# DCDC-LMR16030.net
KiCad netlist of a schematic drawn in Altium Designer
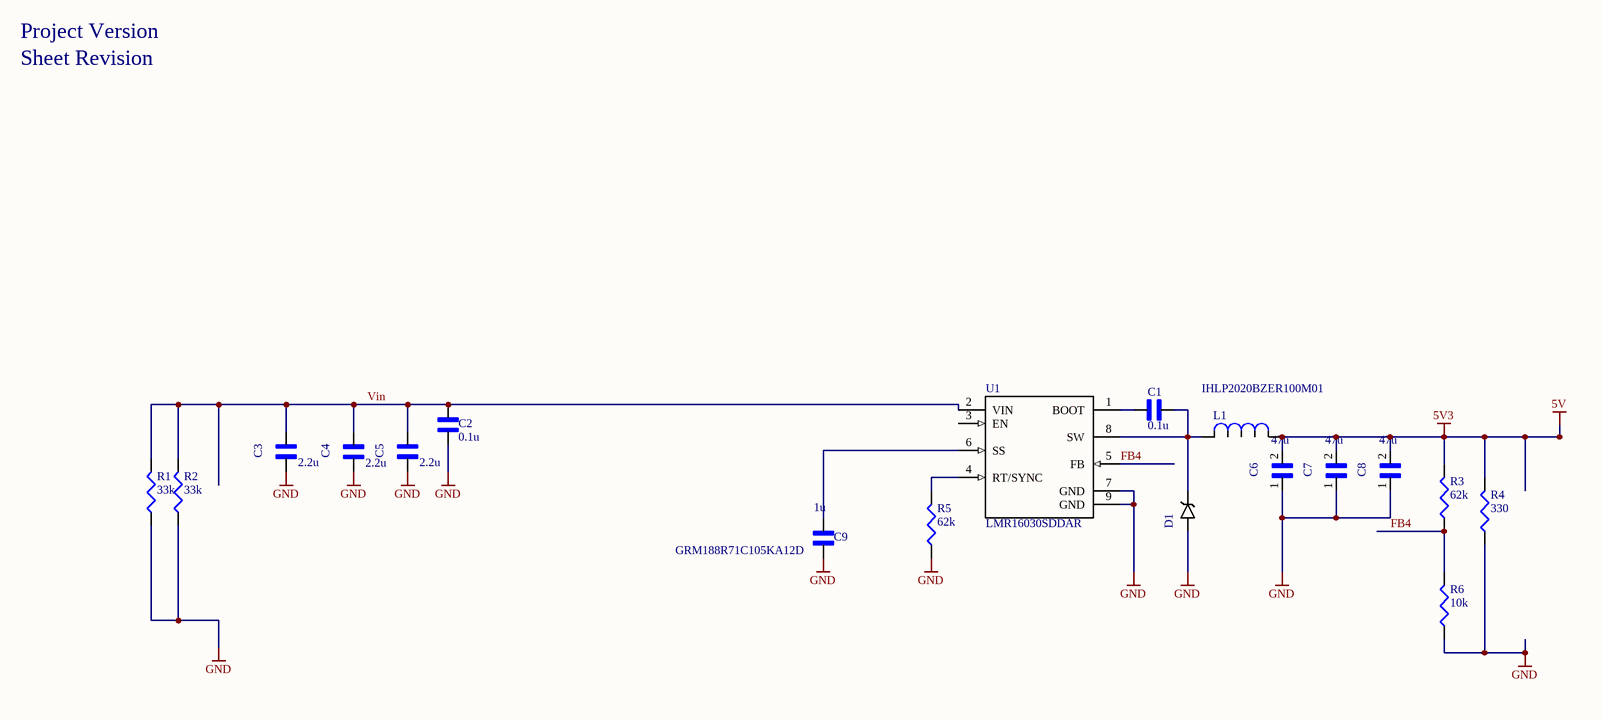
[diagram p0: DCDC-LMR16030.SchDoc]

(export (version "E")
  (design (tool "Eeschema 10.0.6"))
  (components
    (comp (ref "C1")
      (value "0.1u")
      (footprint "CAPC1005X55N")
      (description "GCM155R71H104KE02D, Чип 0402 X7R 0.1uF +10% 50V,Конденсатор")
      (fields (field (name "MF") "Murata") (field (name "MP") "GCM155R71H104KE02D"))
      (libsource (lib "") (part "GCM155R71H104KE02D_1"))
    )
    (comp (ref "C2")
      (value "0.1u")
      (footprint "CAPC1005X55N")
      (description "GCM155R71H104KE02D, Чип 0402 X7R 0.1uF +10% 50V,Конденсатор")
      (fields (field (name "MF") "Murata") (field (name "MP") "GCM155R71H104KE02D"))
      (libsource (lib "lib") (part "GCM155R71H104KE02D"))
    )
    (comp (ref "C3")
      (value "2.2u")
      (footprint "*CAP3216X125N")
      (description "1206 2.2 uF 50 V В±10% Tolerance X7R SMT Multilayer Ceramic Capacitor")
      (fields (field (name "MF") "Murata Electronics") (field (name "MP") "GRM31CR71H225KA88L"))
      (libsource (lib "lib") (part "GRM31CR71H225KA88L"))
    )
    (comp (ref "C4")
      (value "2.2u")
      (footprint "*CAP3216X125N")
      (description "1206 2.2 uF 50 V В±10% Tolerance X7R SMT Multilayer Ceramic Capacitor")
      (fields (field (name "MF") "Murata Electronics") (field (name "MP") "GRM31CR71H225KA88L"))
      (libsource (lib "lib") (part "GRM31CR71H225KA88L"))
    )
    (comp (ref "C5")
      (value "2.2u")
      (footprint "*CAP3216X125N")
      (description "1206 2.2 uF 50 V В±10% Tolerance X7R SMT Multilayer Ceramic Capacitor")
      (fields (field (name "MF") "Murata Electronics") (field (name "MP") "GRM31CR71H225KA88L"))
      (libsource (lib "lib") (part "GRM31CR71H225KA88L"))
    )
    (comp (ref "C6")
      (value "47u")
      (footprint "*CAPC3216X125N")
      (description "Multilayer Ceramic Capacitor, GRM Series, 47 - F, - 10%, X5R, 10 V, 1206 [3216 Metric]")
      (fields (field (name "MF") "Murata Electronics") (field (name "MP") "GRM31CR61A476KE15L"))
      (libsource (lib "lib") (part "GRM31CR61A476KE15L"))
    )
    (comp (ref "C7")
      (value "47u")
      (footprint "*CAPC3216X125N")
      (description "Multilayer Ceramic Capacitor, GRM Series, 47 - F, - 10%, X5R, 10 V, 1206 [3216 Metric]")
      (fields (field (name "MF") "Murata Electronics") (field (name "MP") "GRM31CR61A476KE15L"))
      (libsource (lib "lib") (part "GRM31CR61A476KE15L"))
    )
    (comp (ref "C8")
      (value "47u")
      (footprint "*CAPC3216X125N")
      (description "Multilayer Ceramic Capacitor, GRM Series, 47 - F, - 10%, X5R, 10 V, 1206 [3216 Metric]")
      (fields (field (name "MF") "Murata Electronics") (field (name "MP") "GRM31CR61A476KE15L"))
      (libsource (lib "lib") (part "GRM31CR61A476KE15L"))
    )
    (comp (ref "C9")
      (value "GRM188R71C105KA12D")
      (footprint "CAPC1608X90N")
      (description "SMD Capacitor X7R(EIA) with Capacitance: 1.0uF Tol. 10%. Rated Voltage: 16Vdc")
      (fields (field (name "MF") "Murata Electronics") (field (name "ALTIUM_VALUE") "1u"))
      (libsource (lib "lib") (part "GRM188R71C105KA12D"))
    )
    (comp (ref "D1")
      (value "SK56")
      (footprint "*SMB_P6SMB62AT3G(Primary)")
      (description "Диод Шоттки 5А 60В [SMB / DO-214AA]")
      (fields (field (name "MP") "SK56B") (field (name "MF") "Littelfuse Inc."))
      (libsource (lib "lib") (part "SK56"))
    )
    (comp (ref "L1")
      (value "IHLP2020BZER100M01")
      (footprint "IHLP")
      (description "10ÂµH Shielded Molded Inductor 2.3A 199mOhm Max Nonstandard")
      (fields (field (name "MF") "Vishay Dale"))
      (libsource (lib "lib") (part "IHLP2020BZER100M01"))
    )
    (comp (ref "R1")
      (value "33k")
      (footprint "J1-0603")
      (description "33 kOhms ±1% 0.1W, 1/10W Chip Resistor 0603 (1608 Metric) Moisture Resistant Thick Film")
      (fields (field (name "MF") "Yageo or NXP") (field (name "MP") "RC0603FR-0733KL"))
      (libsource (lib "lib") (part "RC0603FR-0733KL"))
    )
    (comp (ref "R2")
      (value "33k")
      (footprint "J1-0603")
      (description "33 kOhms ±1% 0.1W, 1/10W Chip Resistor 0603 (1608 Metric) Moisture Resistant Thick Film")
      (fields (field (name "MF") "Yageo or NXP") (field (name "MP") "RC0603FR-0733KL"))
      (libsource (lib "lib") (part "RC0603FR-0733KL"))
    )
    (comp (ref "R3")
      (value "62k")
      (footprint "RESC1005X40N")
      (description "0.062Вт 0402 62 кОм, 1%, Чип резистор (SMD)")
      (fields (field (name "MF") "Yageo or NXP") (field (name "MP") "RC0402FR-0762KL"))
      (libsource (lib "lib") (part "RC0402FR-0762KL"))
    )
    (comp (ref "R4")
      (value "330")
      (footprint "J1-0603")
      (description "330 Ohms ±1% 0.1W, 1/10W Chip Resistor 0603 (1608 Metric) Thick Film")
      (fields (field (name "MF") "Yageo or NXP") (field (name "MP") "RC0603FR-07330RL"))
      (libsource (lib "lib") (part "RC0603FR-07330RL"))
    )
    (comp (ref "R5")
      (value "62k")
      (footprint "RESC1005X40N")
      (description "0.062Вт 0402 62 кОм, 1%, Чип резистор (SMD)")
      (fields (field (name "MF") "Yageo or NXP") (field (name "MP") "RC0402FR-0762KL"))
      (libsource (lib "lib") (part "RC0402FR-0762KL"))
    )
    (comp (ref "R6")
      (value "10k")
      (footprint "RESC1005X40N")
      (description "0.062Вт 0402 10 кОм, 1%, Чип резистор (SMD)")
      (fields (field (name "MF") "Yageo or NXP") (field (name "MP") "RC0402FR-0710KL"))
      (libsource (lib "lib") (part "RC0402FR-0710KL"))
    )
    (comp (ref "U1")
      (value "LMR16030SDDAR")
      (footprint "*SOIC127P600X170-9N - duplicate")
      (fields (field (name "MF") "Texas Instruments"))
      (libsource (lib "lib") (part "LMR16030SDDAR"))
    )
  )
  (nets
    (net (code "1") (name "/FB4") (class "Default")
      (node (ref "R3") (pin "1") (pinfunction "1_1") (pintype "passive"))
      (node (ref "R6") (pin "2") (pinfunction "2_2") (pintype "passive"))
      (node (ref "U1") (pin "5") (pinfunction "FB_5") (pintype "input"))
    )
    (net (code "2") (name "/Vin") (class "Default")
      (node (ref "C2") (pin "1") (pinfunction "1_1") (pintype "passive"))
      (node (ref "C3") (pin "1") (pinfunction "1_1") (pintype "passive"))
      (node (ref "C4") (pin "1") (pinfunction "1_1") (pintype "passive"))
      (node (ref "C5") (pin "1") (pinfunction "1_1") (pintype "passive"))
      (node (ref "R1") (pin "2") (pinfunction "2_2") (pintype "passive"))
      (node (ref "R2") (pin "2") (pinfunction "2_2") (pintype "passive"))
      (node (ref "U1") (pin "2") (pinfunction "VIN_2") (pintype "power_in"))
    )
    (net (code "3") (name "5V") (class "Default")
      (node (ref "C6") (pin "2") (pinfunction "2_2") (pintype "passive"))
      (node (ref "C7") (pin "2") (pinfunction "2_2") (pintype "passive"))
      (node (ref "C8") (pin "2") (pinfunction "2_2") (pintype "passive"))
      (node (ref "L1") (pin "1") (pinfunction "1_1") (pintype "passive"))
      (node (ref "R3") (pin "2") (pinfunction "2_2") (pintype "passive"))
      (node (ref "R4") (pin "2") (pinfunction "2_2") (pintype "passive"))
    )
    (net (code "4") (name "GND") (class "Default")
      (node (ref "C2") (pin "2") (pinfunction "2_2") (pintype "passive"))
      (node (ref "C3") (pin "2") (pinfunction "2_2") (pintype "passive"))
      (node (ref "C4") (pin "2") (pinfunction "2_2") (pintype "passive"))
      (node (ref "C5") (pin "2") (pinfunction "2_2") (pintype "passive"))
      (node (ref "C6") (pin "1") (pinfunction "1_1") (pintype "passive"))
      (node (ref "C7") (pin "1") (pinfunction "1_1") (pintype "passive"))
      (node (ref "C8") (pin "1") (pinfunction "1_1") (pintype "passive"))
      (node (ref "C9") (pin "1") (pinfunction "1_1") (pintype "passive"))
      (node (ref "D1") (pin "A") (pinfunction "A_A") (pintype "power_in"))
      (node (ref "R1") (pin "1") (pinfunction "1_1") (pintype "passive"))
      (node (ref "R2") (pin "1") (pinfunction "1_1") (pintype "passive"))
      (node (ref "R4") (pin "1") (pinfunction "1_1") (pintype "passive"))
      (node (ref "R5") (pin "1") (pinfunction "1_1") (pintype "passive"))
      (node (ref "R6") (pin "1") (pinfunction "1_1") (pintype "passive"))
      (node (ref "U1") (pin "7") (pinfunction "GND_7") (pintype "power_in"))
      (node (ref "U1") (pin "9") (pinfunction "GND_9") (pintype "power_in"))
    )
    (net (code "5") (name "Net-(U1-BOOT)") (class "Default")
      (node (ref "C1") (pin "2") (pinfunction "2_2") (pintype "passive"))
      (node (ref "U1") (pin "1") (pinfunction "BOOT_1") (pintype "power_in"))
    )
    (net (code "6") (name "Net-(U1-RT{slash}SYNC)") (class "Default")
      (node (ref "R5") (pin "2") (pinfunction "2_2") (pintype "passive"))
      (node (ref "U1") (pin "4") (pinfunction "RT/SYNC_4") (pintype "input"))
    )
    (net (code "7") (name "Net-(U1-SS)") (class "Default")
      (node (ref "C9") (pin "2") (pinfunction "2_2") (pintype "passive"))
      (node (ref "U1") (pin "6") (pinfunction "SS_6") (pintype "input"))
    )
    (net (code "8") (name "Net-(U1-SW)") (class "Default")
      (node (ref "C1") (pin "1") (pinfunction "1_1") (pintype "passive"))
      (node (ref "D1") (pin "C") (pinfunction "C_C") (pintype "power_in"))
      (node (ref "L1") (pin "2") (pinfunction "2_2") (pintype "passive"))
      (node (ref "U1") (pin "8") (pinfunction "SW_8") (pintype "power_in"))
    )
    (net (code "9") (name "unconnected-(U1-EN-Pad3)") (class "Default")
      (node (ref "U1") (pin "3") (pinfunction "EN_3") (pintype "input"))
    )
  )
)
